# eagle_ChristmasLights.net
KiCad netlist of a schematic drawn in EAGLE
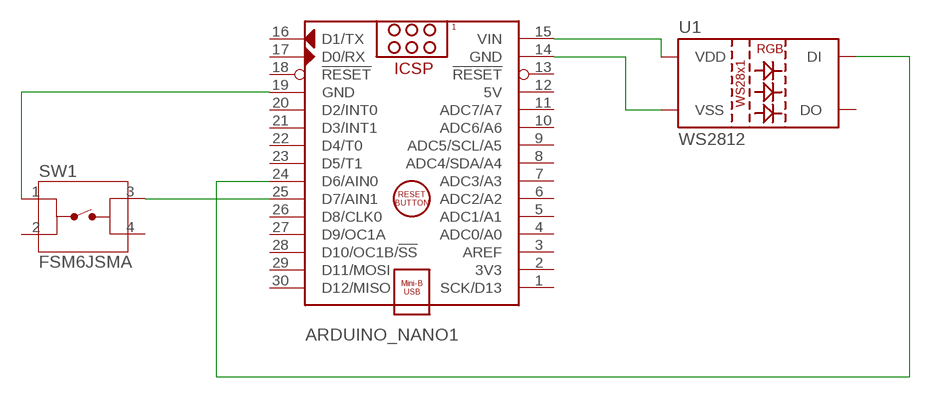
[diagram p0: schematic, sheet 1]

(export (version "E")
  (design (tool "Eeschema 10.0.6"))
  (components
    (comp (ref "ARDUINO_NANO1")
      (value "ARDUINO_NANO")
      (footprint "eagle-import:ARDUINO_NANO")
      (libsource (lib "eagle-import") (part "ARDUINO_NANO"))
    )
    (comp (ref "SW1")
      (value "FSM6JSMA")
      (footprint "eagle-import:FSM6JSMA")
      (fields
        (field (name "DIGIKEY_PART_NUMBER") "450-1133-ND")
        (field (name "MANUFACTURER") "TE Connectivity ALCOSWITCH Switches")
        (field (name "CREATED_BY") "PCBLayout.com")
      )
      (libsource (lib "eagle-import") (part "FSM6JSMA"))
    )
    (comp (ref "U1")
      (value "WS2812")
      (footprint "eagle-import:LED-TRICOLOR-5050-IC")
      (libsource (lib "eagle-import") (part "WS2812{dblquote}"))
    )
  )
  (nets
    (net (code "1") (name "/5V") (class "Default")
      (node (ref "ARDUINO_NANO1") (pin "12") (pinfunction "5V_12") (pintype "power_in"))
    )
    (net (code "2") (name "Net-(ARDUINO_NANO1-D6{slash}AIN0)") (class "Default")
      (node (ref "ARDUINO_NANO1") (pin "24") (pinfunction "D6/AIN0_24") (pintype "bidirectional"))
      (node (ref "U1") (pin "2") (pinfunction "DI_2") (pintype "bidirectional"))
    )
    (net (code "3") (name "Net-(ARDUINO_NANO1-D7{slash}AIN1)") (class "Default")
      (node (ref "ARDUINO_NANO1") (pin "25") (pinfunction "D7/AIN1_25") (pintype "bidirectional"))
      (node (ref "SW1") (pin "3") (pinfunction "3_3") (pintype "passive"))
    )
    (net (code "4") (name "Net-(ARDUINO_NANO1-GND-Pad19)") (class "Default")
      (node (ref "ARDUINO_NANO1") (pin "19") (pinfunction "GND_19") (pintype "power_in"))
      (node (ref "SW1") (pin "1") (pinfunction "1_1") (pintype "passive"))
    )
    (net (code "5") (name "Net-(ARDUINO_NANO1-VIN)") (class "Default")
      (node (ref "ARDUINO_NANO1") (pin "15") (pinfunction "VIN_15") (pintype "power_in"))
      (node (ref "U1") (pin "3") (pinfunction "VDD_3") (pintype "bidirectional"))
      (node (ref "U1") (pin "5") (pinfunction "VDD_5") (pintype "bidirectional"))
    )
    (net (code "6") (name "Net-(U1-VSS)") (class "Default")
      (node (ref "ARDUINO_NANO1") (pin "14") (pinfunction "GND_14") (pintype "power_in"))
      (node (ref "U1") (pin "6") (pinfunction "VSS_6") (pintype "bidirectional"))
    )
    (net (code "7") (name "unconnected-(ARDUINO_NANO1-3V3-Pad2)") (class "Default")
      (node (ref "ARDUINO_NANO1") (pin "2") (pinfunction "3V3_2") (pintype "output"))
    )
    (net (code "8") (name "unconnected-(ARDUINO_NANO1-ADC0{slash}A0-Pad4)") (class "Default")
      (node (ref "ARDUINO_NANO1") (pin "4") (pinfunction "ADC0/A0_4") (pintype "bidirectional"))
    )
    (net (code "9") (name "unconnected-(ARDUINO_NANO1-ADC1{slash}A1-Pad5)") (class "Default")
      (node (ref "ARDUINO_NANO1") (pin "5") (pinfunction "ADC1/A1_5") (pintype "bidirectional"))
    )
    (net (code "10") (name "unconnected-(ARDUINO_NANO1-ADC2{slash}A2-Pad6)") (class "Default")
      (node (ref "ARDUINO_NANO1") (pin "6") (pinfunction "ADC2/A2_6") (pintype "bidirectional"))
    )
    (net (code "11") (name "unconnected-(ARDUINO_NANO1-ADC3{slash}A3-Pad7)") (class "Default")
      (node (ref "ARDUINO_NANO1") (pin "7") (pinfunction "ADC3/A3_7") (pintype "bidirectional"))
    )
    (net (code "12") (name "unconnected-(ARDUINO_NANO1-ADC4{slash}SDA{slash}A4-Pad8)") (class "Default")
      (node (ref "ARDUINO_NANO1") (pin "8") (pinfunction "ADC4/SDA/A4_8") (pintype "bidirectional"))
    )
    (net (code "13") (name "unconnected-(ARDUINO_NANO1-ADC5{slash}SCL{slash}A5-Pad9)") (class "Default")
      (node (ref "ARDUINO_NANO1") (pin "9") (pinfunction "ADC5/SCL/A5_9") (pintype "bidirectional"))
    )
    (net (code "14") (name "unconnected-(ARDUINO_NANO1-ADC6{slash}A6-Pad10)") (class "Default")
      (node (ref "ARDUINO_NANO1") (pin "10") (pinfunction "ADC6/A6_10") (pintype "bidirectional"))
    )
    (net (code "15") (name "unconnected-(ARDUINO_NANO1-ADC7{slash}A7-Pad11)") (class "Default")
      (node (ref "ARDUINO_NANO1") (pin "11") (pinfunction "ADC7/A7_11") (pintype "bidirectional"))
    )
    (net (code "16") (name "unconnected-(ARDUINO_NANO1-AREF-Pad3)") (class "Default")
      (node (ref "ARDUINO_NANO1") (pin "3") (pinfunction "AREF_3") (pintype "input"))
    )
    (net (code "17") (name "unconnected-(ARDUINO_NANO1-D0{slash}RX-Pad17)") (class "Default")
      (node (ref "ARDUINO_NANO1") (pin "17") (pinfunction "D0/RX_17") (pintype "bidirectional"))
    )
    (net (code "18") (name "unconnected-(ARDUINO_NANO1-D1{slash}TX-Pad16)") (class "Default")
      (node (ref "ARDUINO_NANO1") (pin "16") (pinfunction "D1/TX_16") (pintype "bidirectional"))
    )
    (net (code "19") (name "unconnected-(ARDUINO_NANO1-D2{slash}INT0-Pad20)") (class "Default")
      (node (ref "ARDUINO_NANO1") (pin "20") (pinfunction "D2/INT0_20") (pintype "bidirectional"))
    )
    (net (code "20") (name "unconnected-(ARDUINO_NANO1-D3{slash}INT1-Pad21)") (class "Default")
      (node (ref "ARDUINO_NANO1") (pin "21") (pinfunction "D3/INT1_21") (pintype "bidirectional"))
    )
    (net (code "21") (name "unconnected-(ARDUINO_NANO1-D4{slash}T0-Pad22)") (class "Default")
      (node (ref "ARDUINO_NANO1") (pin "22") (pinfunction "D4/T0_22") (pintype "bidirectional"))
    )
    (net (code "22") (name "unconnected-(ARDUINO_NANO1-D5{slash}T1-Pad23)") (class "Default")
      (node (ref "ARDUINO_NANO1") (pin "23") (pinfunction "D5/T1_23") (pintype "bidirectional"))
    )
    (net (code "23") (name "unconnected-(ARDUINO_NANO1-D8{slash}CLK0-Pad26)") (class "Default")
      (node (ref "ARDUINO_NANO1") (pin "26") (pinfunction "D8/CLK0_26") (pintype "bidirectional"))
    )
    (net (code "24") (name "unconnected-(ARDUINO_NANO1-D9{slash}OC1A-Pad27)") (class "Default")
      (node (ref "ARDUINO_NANO1") (pin "27") (pinfunction "D9/OC1A_27") (pintype "bidirectional"))
    )
    (net (code "25") (name "unconnected-(ARDUINO_NANO1-D10{slash}OC1B{slash}~{SS}-Pad28)") (class "Default")
      (node (ref "ARDUINO_NANO1") (pin "28") (pinfunction "D10/OC1B/~{SS}_28") (pintype "bidirectional"))
    )
    (net (code "26") (name "unconnected-(ARDUINO_NANO1-D11{slash}MOSI-Pad29)") (class "Default")
      (node (ref "ARDUINO_NANO1") (pin "29") (pinfunction "D11/MOSI_29") (pintype "bidirectional"))
    )
    (net (code "27") (name "unconnected-(ARDUINO_NANO1-D12{slash}MISO-Pad30)") (class "Default")
      (node (ref "ARDUINO_NANO1") (pin "30") (pinfunction "D12/MISO_30") (pintype "bidirectional"))
    )
    (net (code "28") (name "unconnected-(ARDUINO_NANO1-SCK{slash}D13-Pad1)") (class "Default")
      (node (ref "ARDUINO_NANO1") (pin "1") (pinfunction "SCK/D13_1") (pintype "bidirectional"))
    )
    (net (code "29") (name "unconnected-(ARDUINO_NANO1-~{RESET}-Pad13)") (class "Default")
      (node (ref "ARDUINO_NANO1") (pin "13") (pinfunction "~{RESET}_13") (pintype "input"))
    )
    (net (code "30") (name "unconnected-(ARDUINO_NANO1-~{RESET}-Pad18)") (class "Default")
      (node (ref "ARDUINO_NANO1") (pin "18") (pinfunction "~{RESET}_18") (pintype "input"))
    )
    (net (code "31") (name "unconnected-(SW1-Pad2)") (class "Default")
      (node (ref "SW1") (pin "2") (pinfunction "2_2") (pintype "passive"))
    )
    (net (code "32") (name "unconnected-(SW1-Pad4)") (class "Default")
      (node (ref "SW1") (pin "4") (pinfunction "4_4") (pintype "passive"))
    )
    (net (code "33") (name "unconnected-(U1-DO-Pad1)") (class "Default")
      (node (ref "U1") (pin "1") (pinfunction "DO_1") (pintype "bidirectional"))
    )
  )
)
